# Processor.net
KiCad netlist of a schematic drawn in Altium Designer
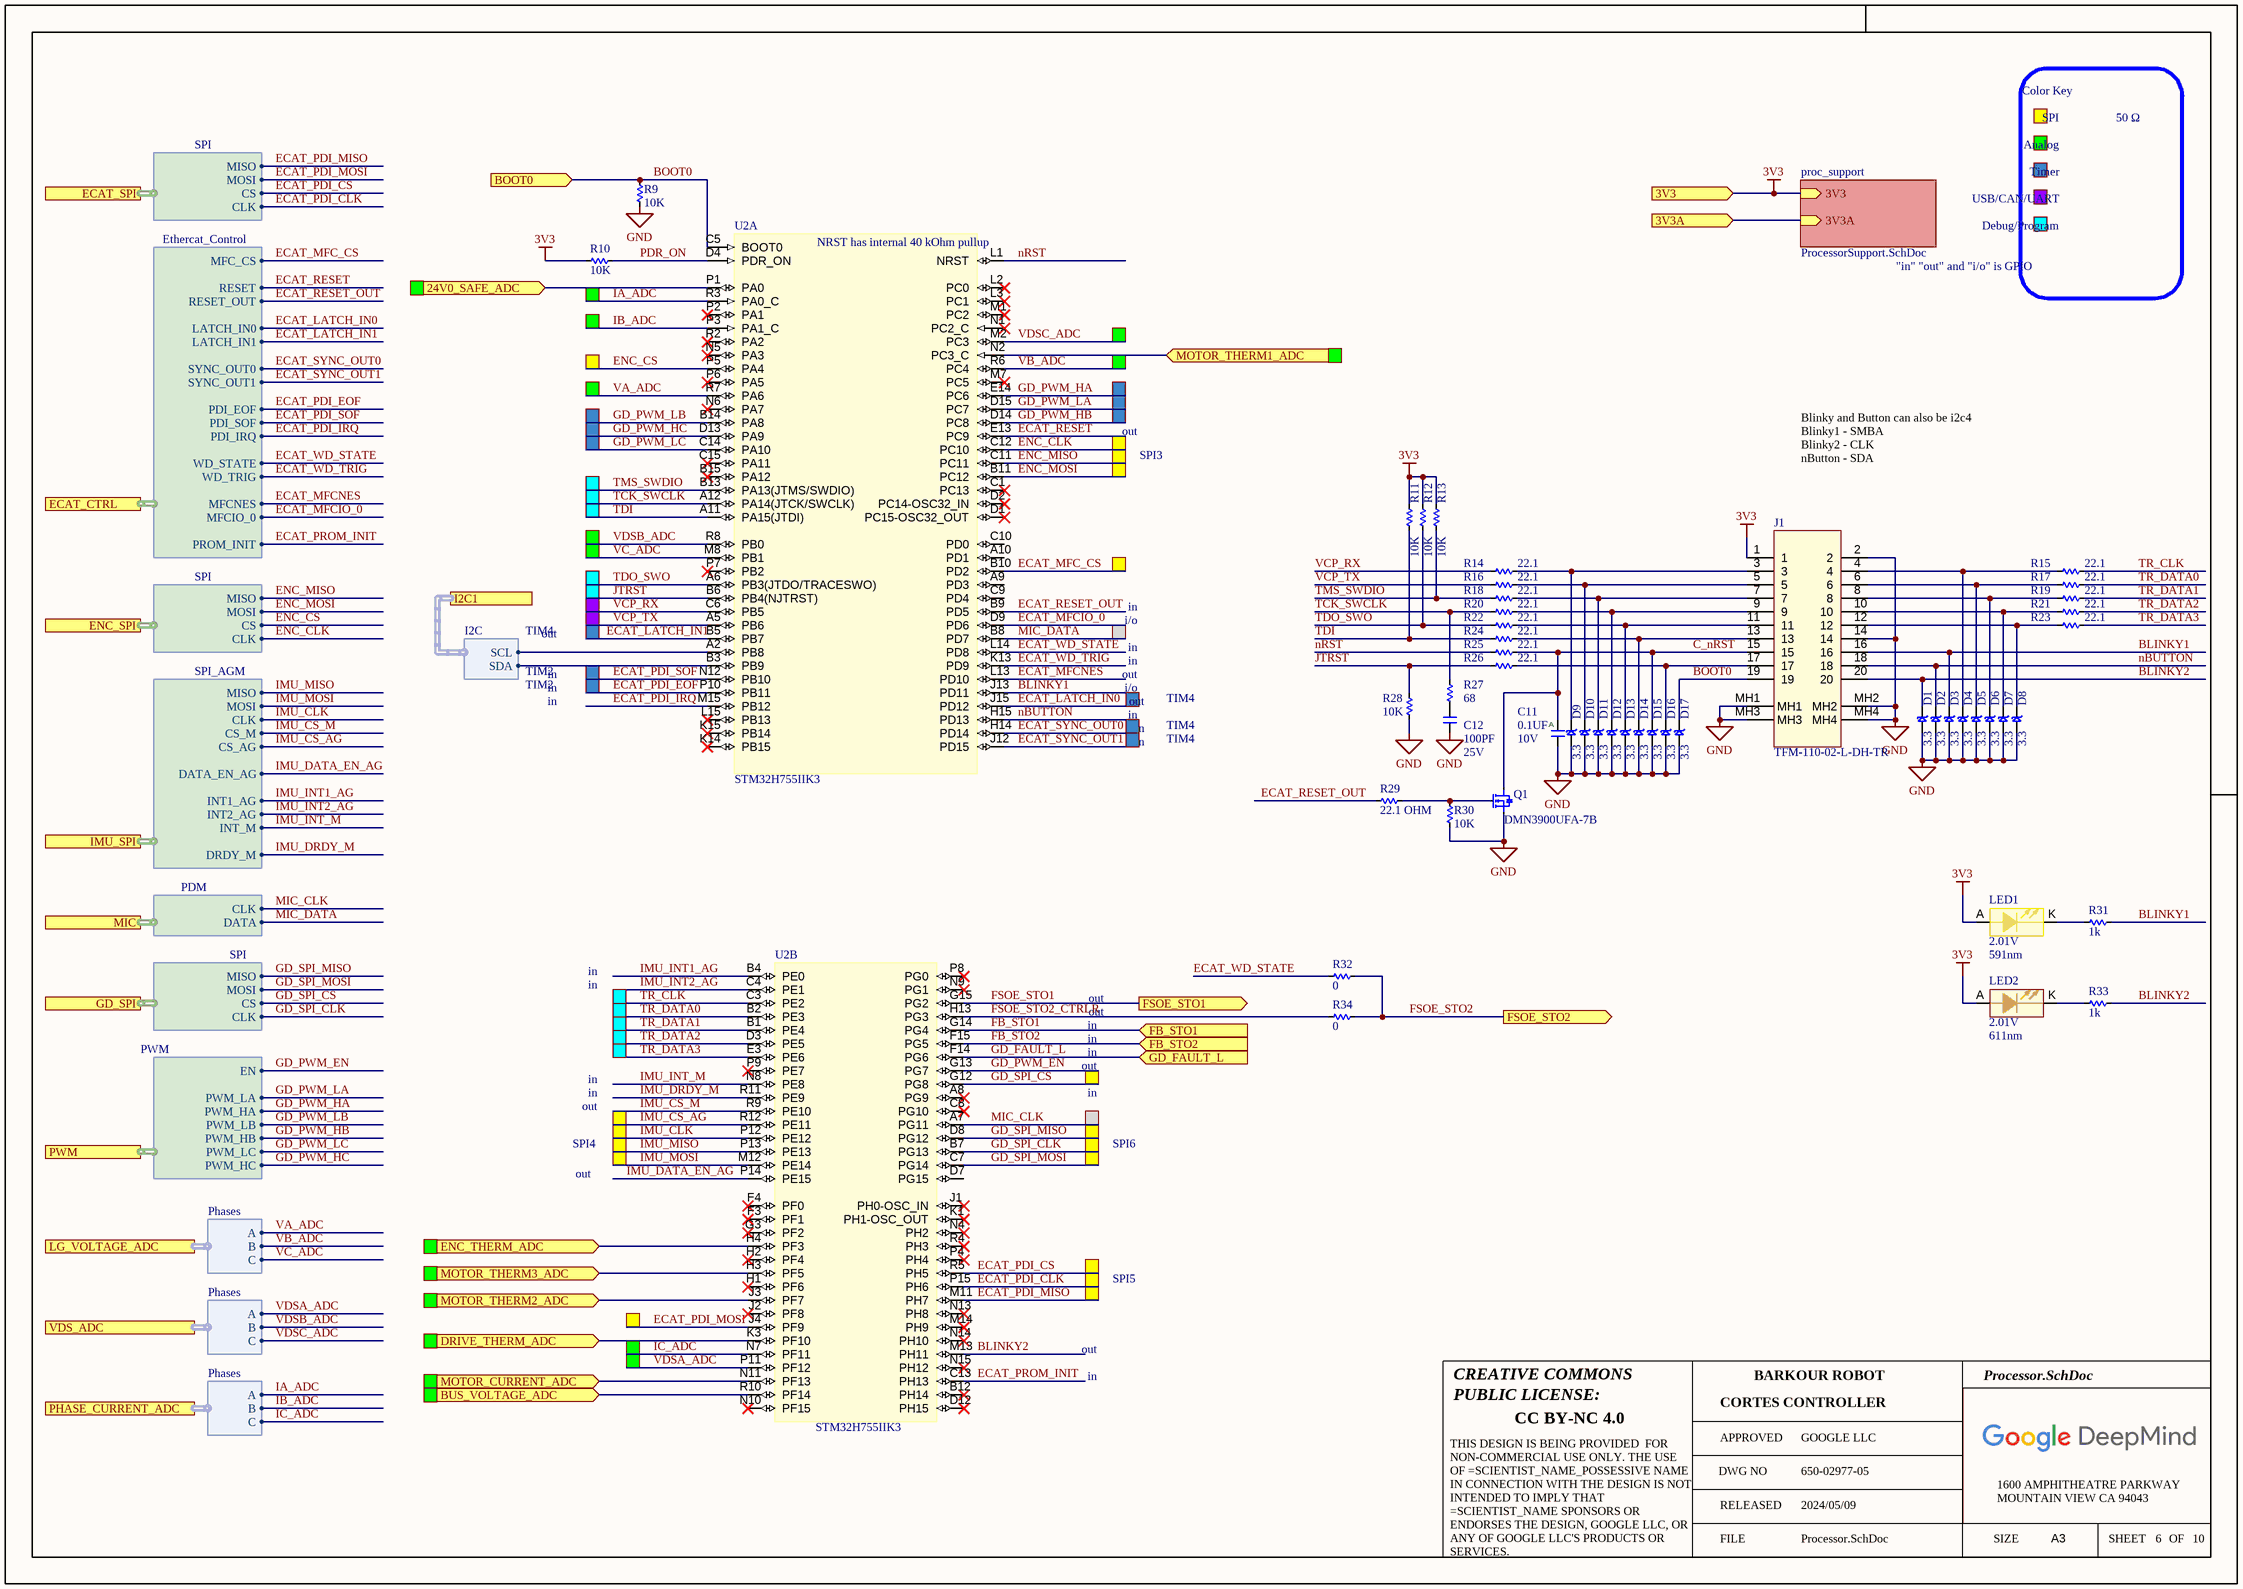
[diagram p0: Processor.SchDoc]

(export (version "E")
  (design (tool "Eeschema 10.0.6"))
  (components
    (comp (ref "C11")
      (value "0.1UF")
      (footprint "C0201Y")
      (description "CAP, CER, X6S, 0.1uF, 10V, 10%, 0201, AUTOGRADE")
      (fields (field (name "MFG") "MURATA") (field (name "VOLTAGE") "10V") (field (name "TOLERANCE") "10%"))
      (libsource (lib "AltiumReleaseLibDB") (part "__Template_Cap_Auto"))
    )
    (comp (ref "C12")
      (value "100PF")
      (footprint "C0201Y")
      (description "CAP, CER, X7R, 100pF, 25V, 10%, 0201, 0.33mm T")
      (fields (field (name "MFG") "MURATA") (field (name "VOLTAGE") "25V") (field (name "TOLERANCE") "10%"))
      (libsource (lib "AltiumReleaseLibDB") (part "__Template_Cap"))
    )
    (comp (ref "D1")
      (value "3.3")
      (footprint "SOD1060X40")
      (description "TVS, DIODE, UNIDIR, 3.3VRWM, 4.8VBR, 7.8VCL, SOD-923")
      (fields (field (name "MFG") "ON Semiconductor"))
      (libsource (lib "AltiumReleaseLibDB") (part "__Template_Diode_TVS_A/K"))
    )
    (comp (ref "D2")
      (value "3.3")
      (footprint "SOD1060X40")
      (description "TVS, DIODE, UNIDIR, 3.3VRWM, 4.8VBR, 7.8VCL, SOD-923")
      (fields (field (name "MFG") "ON Semiconductor"))
      (libsource (lib "AltiumReleaseLibDB") (part "__Template_Diode_TVS_A/K"))
    )
    (comp (ref "D3")
      (value "3.3")
      (footprint "SOD1060X40")
      (description "TVS, DIODE, UNIDIR, 3.3VRWM, 4.8VBR, 7.8VCL, SOD-923")
      (fields (field (name "MFG") "ON Semiconductor"))
      (libsource (lib "AltiumReleaseLibDB") (part "__Template_Diode_TVS_A/K"))
    )
    (comp (ref "D4")
      (value "3.3")
      (footprint "SOD1060X40")
      (description "TVS, DIODE, UNIDIR, 3.3VRWM, 4.8VBR, 7.8VCL, SOD-923")
      (fields (field (name "MFG") "ON Semiconductor"))
      (libsource (lib "AltiumReleaseLibDB") (part "__Template_Diode_TVS_A/K"))
    )
    (comp (ref "D5")
      (value "3.3")
      (footprint "SOD1060X40")
      (description "TVS, DIODE, UNIDIR, 3.3VRWM, 4.8VBR, 7.8VCL, SOD-923")
      (fields (field (name "MFG") "ON Semiconductor"))
      (libsource (lib "AltiumReleaseLibDB") (part "__Template_Diode_TVS_A/K"))
    )
    (comp (ref "D6")
      (value "3.3")
      (footprint "SOD1060X40")
      (description "TVS, DIODE, UNIDIR, 3.3VRWM, 4.8VBR, 7.8VCL, SOD-923")
      (fields (field (name "MFG") "ON Semiconductor"))
      (libsource (lib "AltiumReleaseLibDB") (part "__Template_Diode_TVS_A/K"))
    )
    (comp (ref "D7")
      (value "3.3")
      (footprint "SOD1060X40")
      (description "TVS, DIODE, UNIDIR, 3.3VRWM, 4.8VBR, 7.8VCL, SOD-923")
      (fields (field (name "MFG") "ON Semiconductor"))
      (libsource (lib "AltiumReleaseLibDB") (part "__Template_Diode_TVS_A/K"))
    )
    (comp (ref "D8")
      (value "3.3")
      (footprint "SOD1060X40")
      (description "TVS, DIODE, UNIDIR, 3.3VRWM, 4.8VBR, 7.8VCL, SOD-923")
      (fields (field (name "MFG") "ON Semiconductor"))
      (libsource (lib "AltiumReleaseLibDB") (part "__Template_Diode_TVS_A/K"))
    )
    (comp (ref "D9")
      (value "3.3")
      (footprint "SOD1060X40")
      (description "TVS, DIODE, UNIDIR, 3.3VRWM, 4.8VBR, 7.8VCL, SOD-923")
      (fields (field (name "MFG") "ON Semiconductor"))
      (libsource (lib "AltiumReleaseLibDB") (part "__Template_Diode_TVS_A/K"))
    )
    (comp (ref "D10")
      (value "3.3")
      (footprint "SOD1060X40")
      (description "TVS, DIODE, UNIDIR, 3.3VRWM, 4.8VBR, 7.8VCL, SOD-923")
      (fields (field (name "MFG") "ON Semiconductor"))
      (libsource (lib "AltiumReleaseLibDB") (part "__Template_Diode_TVS_A/K"))
    )
    (comp (ref "D11")
      (value "3.3")
      (footprint "SOD1060X40")
      (description "TVS, DIODE, UNIDIR, 3.3VRWM, 4.8VBR, 7.8VCL, SOD-923")
      (fields (field (name "MFG") "ON Semiconductor"))
      (libsource (lib "AltiumReleaseLibDB") (part "__Template_Diode_TVS_A/K"))
    )
    (comp (ref "D12")
      (value "3.3")
      (footprint "SOD1060X40")
      (description "TVS, DIODE, UNIDIR, 3.3VRWM, 4.8VBR, 7.8VCL, SOD-923")
      (fields (field (name "MFG") "ON Semiconductor"))
      (libsource (lib "AltiumReleaseLibDB") (part "__Template_Diode_TVS_A/K"))
    )
    (comp (ref "D13")
      (value "3.3")
      (footprint "SOD1060X40")
      (description "TVS, DIODE, UNIDIR, 3.3VRWM, 4.8VBR, 7.8VCL, SOD-923")
      (fields (field (name "MFG") "ON Semiconductor"))
      (libsource (lib "AltiumReleaseLibDB") (part "__Template_Diode_TVS_A/K"))
    )
    (comp (ref "D14")
      (value "3.3")
      (footprint "SOD1060X40")
      (description "TVS, DIODE, UNIDIR, 3.3VRWM, 4.8VBR, 7.8VCL, SOD-923")
      (fields (field (name "MFG") "ON Semiconductor"))
      (libsource (lib "AltiumReleaseLibDB") (part "__Template_Diode_TVS_A/K"))
    )
    (comp (ref "D15")
      (value "3.3")
      (footprint "SOD1060X40")
      (description "TVS, DIODE, UNIDIR, 3.3VRWM, 4.8VBR, 7.8VCL, SOD-923")
      (fields (field (name "MFG") "ON Semiconductor"))
      (libsource (lib "AltiumReleaseLibDB") (part "__Template_Diode_TVS_A/K"))
    )
    (comp (ref "D16")
      (value "3.3")
      (footprint "SOD1060X40")
      (description "TVS, DIODE, UNIDIR, 3.3VRWM, 4.8VBR, 7.8VCL, SOD-923")
      (fields (field (name "MFG") "ON Semiconductor"))
      (libsource (lib "AltiumReleaseLibDB") (part "__Template_Diode_TVS_A/K"))
    )
    (comp (ref "D17")
      (value "3.3")
      (footprint "SOD1060X40")
      (description "TVS, DIODE, UNIDIR, 3.3VRWM, 4.8VBR, 7.8VCL, SOD-923")
      (fields (field (name "MFG") "ON Semiconductor"))
      (libsource (lib "AltiumReleaseLibDB") (part "__Template_Diode_TVS_A/K"))
    )
    (comp (ref "J1")
      (value "~")
      (footprint "SAMTEC_TFM-110-02-L-DH")
      (description "CONN, HDR, SHRD, RA, 2x10, 1.27MM P, 6.02MM h, GOLD, TH")
      (fields (field (name "MFG") "Samtec Inc") (field (name "MFG P/N") "TFM-110-02-L-DH-TR"))
      (libsource (lib "AltiumReleaseLibDB") (part "__Template_Connector_2X10_4MH"))
    )
    (comp (ref "LED1")
      (value "__Template_LED_YELLOW_AK")
      (footprint "LED_APG0603SYC-TT")
      (description "LED, YELLOW, 591NM, 10mA, CLEAR, 0201")
      (fields
        (field (name "MFG") "Kingbright")
        (field (name "VOLTAGE – FORWARD (VF) (MAX) @ IF") "2.01V")
        (field (name "COLOR / WAVELENGTH") "591nm")
      )
      (libsource (lib "AltiumReleaseLibDB") (part "__Template_LED_YELLOW_AK"))
    )
    (comp (ref "LED2")
      (value "__Template_LED_ORANGE_AK")
      (footprint "LED_APG0603SYC-TT")
      (description "LED, ORANGE, 611NM, 10mA, CLEAR, 0201")
      (fields
        (field (name "MFG") "Kingbright")
        (field (name "VOLTAGE – FORWARD (VF) (MAX) @ IF") "2.01V")
        (field (name "COLOR / WAVELENGTH") "611nm")
      )
      (libsource (lib "AltiumReleaseLibDB") (part "__Template_LED_ORANGE_AK"))
    )
    (comp (ref "Q1")
      (value "NFET_DMN3900UFA")
      (footprint "3XDFN")
      (description "MOSFET, N-CH, 30V, 0.55A, DMN3900")
      (fields (field (name "MFG") "Diodes Incorporated") (field (name "MFG P/N") "DMN3900UFA-7B"))
      (libsource (lib "AltiumReleaseLibDB") (part "NFET_DMN3900UFA"))
    )
    (comp (ref "R9")
      (value "10K")
      (footprint "R0201_H0.26MM")
      (description "RES, 10K, 1%, 1/20W, 0201, AUTOGRADE")
      (fields (field (name "MFG") "PANASONIC") (field (name "POWER") "1/20W"))
      (libsource (lib "AltiumReleaseLibDB") (part "__Template_Resistor"))
    )
    (comp (ref "R10")
      (value "10K")
      (footprint "R0201_H0.26MM")
      (description "RES, 10K, 1%, 1/20W, 0201, AUTOGRADE")
      (fields (field (name "MFG") "PANASONIC") (field (name "POWER") "1/20W"))
      (libsource (lib "AltiumReleaseLibDB") (part "__Template_Resistor"))
    )
    (comp (ref "R11")
      (value "10K")
      (footprint "R0201_H0.26MM")
      (description "RES, 10K, 1%, 1/20W, 0201, AUTOGRADE")
      (fields (field (name "MFG") "PANASONIC") (field (name "POWER") "1/20W"))
      (libsource (lib "AltiumReleaseLibDB") (part "__Template_Resistor"))
    )
    (comp (ref "R12")
      (value "10K")
      (footprint "R0201_H0.26MM")
      (description "RES, 10K, 1%, 1/20W, 0201, AUTOGRADE")
      (fields (field (name "MFG") "PANASONIC") (field (name "POWER") "1/20W"))
      (libsource (lib "AltiumReleaseLibDB") (part "__Template_Resistor"))
    )
    (comp (ref "R13")
      (value "10K")
      (footprint "R0201_H0.26MM")
      (description "RES, 10K, 1%, 1/20W, 0201, AUTOGRADE")
      (fields (field (name "MFG") "PANASONIC") (field (name "POWER") "1/20W"))
      (libsource (lib "AltiumReleaseLibDB") (part "__Template_Resistor"))
    )
    (comp (ref "R14")
      (value "22.1")
      (footprint "R0201_H0.26MM")
      (description "RES, 22.1, 1%, 1/20W, 0201, AUTOGRADE")
      (fields (field (name "MFG") "Panasonic Electronic Components") (field (name "POWER") "0.05W, 1/20W"))
      (libsource (lib "AltiumReleaseLibDB") (part "__Template_Resistor"))
    )
    (comp (ref "R15")
      (value "22.1")
      (footprint "R0201_H0.26MM")
      (description "RES, 22.1, 1%, 1/20W, 0201, AUTOGRADE")
      (fields (field (name "MFG") "Panasonic Electronic Components") (field (name "POWER") "0.05W, 1/20W"))
      (libsource (lib "AltiumReleaseLibDB") (part "__Template_Resistor"))
    )
    (comp (ref "R16")
      (value "22.1")
      (footprint "R0201_H0.26MM")
      (description "RES, 22.1, 1%, 1/20W, 0201, AUTOGRADE")
      (fields (field (name "MFG") "Panasonic Electronic Components") (field (name "POWER") "0.05W, 1/20W"))
      (libsource (lib "AltiumReleaseLibDB") (part "__Template_Resistor"))
    )
    (comp (ref "R17")
      (value "22.1")
      (footprint "R0201_H0.26MM")
      (description "RES, 22.1, 1%, 1/20W, 0201, AUTOGRADE")
      (fields (field (name "MFG") "Panasonic Electronic Components") (field (name "POWER") "0.05W, 1/20W"))
      (libsource (lib "AltiumReleaseLibDB") (part "__Template_Resistor"))
    )
    (comp (ref "R18")
      (value "22.1")
      (footprint "R0201_H0.26MM")
      (description "RES, 22.1, 1%, 1/20W, 0201, AUTOGRADE")
      (fields (field (name "MFG") "Panasonic Electronic Components") (field (name "POWER") "0.05W, 1/20W"))
      (libsource (lib "AltiumReleaseLibDB") (part "__Template_Resistor"))
    )
    (comp (ref "R19")
      (value "22.1")
      (footprint "R0201_H0.26MM")
      (description "RES, 22.1, 1%, 1/20W, 0201, AUTOGRADE")
      (fields (field (name "MFG") "Panasonic Electronic Components") (field (name "POWER") "0.05W, 1/20W"))
      (libsource (lib "AltiumReleaseLibDB") (part "__Template_Resistor"))
    )
    (comp (ref "R20")
      (value "22.1")
      (footprint "R0201_H0.26MM")
      (description "RES, 22.1, 1%, 1/20W, 0201, AUTOGRADE")
      (fields (field (name "MFG") "Panasonic Electronic Components") (field (name "POWER") "0.05W, 1/20W"))
      (libsource (lib "AltiumReleaseLibDB") (part "__Template_Resistor"))
    )
    (comp (ref "R21")
      (value "22.1")
      (footprint "R0201_H0.26MM")
      (description "RES, 22.1, 1%, 1/20W, 0201, AUTOGRADE")
      (fields (field (name "MFG") "Panasonic Electronic Components") (field (name "POWER") "0.05W, 1/20W"))
      (libsource (lib "AltiumReleaseLibDB") (part "__Template_Resistor"))
    )
    (comp (ref "R22")
      (value "22.1")
      (footprint "R0201_H0.26MM")
      (description "RES, 22.1, 1%, 1/20W, 0201, AUTOGRADE")
      (fields (field (name "MFG") "Panasonic Electronic Components") (field (name "POWER") "0.05W, 1/20W"))
      (libsource (lib "AltiumReleaseLibDB") (part "__Template_Resistor"))
    )
    (comp (ref "R23")
      (value "22.1")
      (footprint "R0201_H0.26MM")
      (description "RES, 22.1, 1%, 1/20W, 0201, AUTOGRADE")
      (fields (field (name "MFG") "Panasonic Electronic Components") (field (name "POWER") "0.05W, 1/20W"))
      (libsource (lib "AltiumReleaseLibDB") (part "__Template_Resistor"))
    )
    (comp (ref "R24")
      (value "22.1")
      (footprint "R0201_H0.26MM")
      (description "RES, 22.1, 1%, 1/20W, 0201, AUTOGRADE")
      (fields (field (name "MFG") "Panasonic Electronic Components") (field (name "POWER") "0.05W, 1/20W"))
      (libsource (lib "AltiumReleaseLibDB") (part "__Template_Resistor"))
    )
    (comp (ref "R25")
      (value "22.1")
      (footprint "R0201_H0.26MM")
      (description "RES, 22.1, 1%, 1/20W, 0201, AUTOGRADE")
      (fields (field (name "MFG") "Panasonic Electronic Components") (field (name "POWER") "0.05W, 1/20W"))
      (libsource (lib "AltiumReleaseLibDB") (part "__Template_Resistor"))
    )
    (comp (ref "R26")
      (value "22.1")
      (footprint "R0201_H0.26MM")
      (description "RES, 22.1, 1%, 1/20W, 0201, AUTOGRADE")
      (fields (field (name "MFG") "Panasonic Electronic Components") (field (name "POWER") "0.05W, 1/20W"))
      (libsource (lib "AltiumReleaseLibDB") (part "__Template_Resistor"))
    )
    (comp (ref "R27")
      (value "68")
      (footprint "R0201_H0.26MM")
      (description "RES, 68, 1%, 1/20W, 0201, AUTOGRADE")
      (fields (field (name "MFG") "Panasonic Electronic Components") (field (name "POWER") "0.05W, 1/20W"))
      (libsource (lib "AltiumReleaseLibDB") (part "__Template_Resistor"))
    )
    (comp (ref "R28")
      (value "10K")
      (footprint "R0201_H0.26MM")
      (description "RES, 10K, 1%, 1/20W, 0201, AUTOGRADE")
      (fields (field (name "MFG") "PANASONIC") (field (name "POWER") "1/20W"))
      (libsource (lib "AltiumReleaseLibDB") (part "__Template_Resistor"))
    )
    (comp (ref "R29")
      (value "22.1 OHM")
      (footprint "R0201_H0.26MM")
      (description "RES, 22.1, 1%, 1/20W, 0201, AUTOGRADE")
      (fields (field (name "MFG") "Panasonic Electronic Components") (field (name "POWER") "0.05W, 1/20W"))
      (libsource (lib "AltiumReleaseLibDB") (part "__Template_Resistor"))
    )
    (comp (ref "R30")
      (value "10K")
      (footprint "R0201_H0.26MM")
      (description "RES, 10K, 1%, 1/20W, 0201, AUTOGRADE")
      (fields (field (name "MFG") "PANASONIC") (field (name "POWER") "1/20W"))
      (libsource (lib "AltiumReleaseLibDB") (part "__Template_Resistor"))
    )
    (comp (ref "R31")
      (value "1k")
      (footprint "R0201_H0.26MM")
      (description "RES, 1K, 1%, 1/20W, 0201, AUTOGRADE")
      (fields (field (name "MFG") "Bourns Inc.") (field (name "POWER") "0.05W, 1/20W"))
      (libsource (lib "AltiumReleaseLibDB") (part "__Template_Resistor"))
    )
    (comp (ref "R32")
      (value "0")
      (footprint "R0603")
      (description "RES, JUMPER, 0, 1/10W, 0603")
      (fields (field (name "MFG") "ROHM") (field (name "POWER") "1/10W"))
      (libsource (lib "AltiumReleaseLibDB") (part "__Template_Resistor"))
    )
    (comp (ref "R33")
      (value "1k")
      (footprint "R0201_H0.26MM")
      (description "RES, 1K, 1%, 1/20W, 0201, AUTOGRADE")
      (fields (field (name "MFG") "Bourns Inc.") (field (name "POWER") "0.05W, 1/20W"))
      (libsource (lib "AltiumReleaseLibDB") (part "__Template_Resistor"))
    )
    (comp (ref "R34")
      (value "0")
      (footprint "R0603")
      (description "RES, JUMPER, 0, 1/10W, 0603")
      (fields (field (name "MFG") "ROHM") (field (name "POWER") "1/10W"))
      (libsource (lib "AltiumReleaseLibDB") (part "__Template_Resistor"))
    )
    (comp (ref "U2")
      (value "MCU_STM32H755IIK3")
      (footprint "BGS201C65P15X15_1000X1000X60")
      (description "IC, MCU, STM32H755xI, ARM, 32-BIT, 240MHZ, 128 I/O, 2MB, FLASH, 1.62V TO 3.6V, UFBGA-201")
      (fields (field (name "MFG") "STMicroelectronics") (field (name "MFG P/N") "STM32H755IIK3"))
      (libsource (lib "AltiumReleaseLibDB") (part "MCU_STM32H755IIK3"))
    )
  )
  (nets
    (net (code "9") (name "/24V0_SAFE_ADC") (class "Default")
      (node (ref "U2") (pin "P1") (pinfunction "PA0_P1") (pintype "bidirectional"))
    )
    (net (code "10") (name "/BLINKY1") (class "Default")
      (node (ref "D3") (pin "K") (pinfunction "K_K") (pintype "passive"))
      (node (ref "J1") (pin "16") (pinfunction "16_16") (pintype "passive"))
      (node (ref "R31") (pin "1") (pintype "passive"))
      (node (ref "U2") (pin "J13") (pinfunction "PD11_J13") (pintype "bidirectional"))
    )
    (net (code "11") (name "/BLINKY2") (class "Default")
      (node (ref "D1") (pin "K") (pinfunction "K_K") (pintype "passive"))
      (node (ref "J1") (pin "20") (pinfunction "20_20") (pintype "passive"))
      (node (ref "R33") (pin "1") (pintype "passive"))
      (node (ref "U2") (pin "M13") (pinfunction "PH11_M13") (pintype "bidirectional"))
    )
    (net (code "12") (name "/BOOT0") (class "Default")
      (node (ref "D17") (pin "K") (pinfunction "K_K") (pintype "passive"))
      (node (ref "J1") (pin "19") (pinfunction "19_19") (pintype "passive"))
      (node (ref "R9") (pin "2") (pintype "passive"))
      (node (ref "U2") (pin "C5") (pinfunction "BOOT0_C5") (pintype "input"))
    )
    (net (code "13") (name "/BUS_VOLTAGE_ADC") (class "Default")
      (node (ref "U2") (pin "R10") (pinfunction "PF14_R10") (pintype "bidirectional"))
    )
    (net (code "14") (name "/C_nRST") (class "Default")
      (node (ref "C11") (pin "1") (pintype "passive"))
      (node (ref "D15") (pin "K") (pinfunction "K_K") (pintype "passive"))
      (node (ref "J1") (pin "15") (pinfunction "15_15") (pintype "passive"))
      (node (ref "Q1") (pin "3") (pinfunction "D_3") (pintype "passive"))
      (node (ref "R25") (pin "2") (pintype "passive"))
    )
    (net (code "15") (name "/DRIVE_THERM_ADC") (class "Default")
      (node (ref "U2") (pin "K3") (pinfunction "PF10_K3") (pintype "bidirectional"))
    )
    (net (code "16") (name "/ECAT_LATCH_IN0") (class "Default")
      (node (ref "U2") (pin "J15") (pinfunction "PD12_J15") (pintype "bidirectional"))
    )
    (net (code "17") (name "/ECAT_LATCH_IN1") (class "Default")
      (node (ref "U2") (pin "B5") (pinfunction "PB7_B5") (pintype "bidirectional"))
    )
    (net (code "18") (name "/ECAT_MFCIO_0") (class "Default")
      (node (ref "U2") (pin "D9") (pinfunction "PD6_D9") (pintype "bidirectional"))
    )
    (net (code "19") (name "/ECAT_MFCNES") (class "Default")
      (node (ref "U2") (pin "L13") (pinfunction "PD10_L13") (pintype "bidirectional"))
    )
    (net (code "20") (name "/ECAT_MFC_CS") (class "Default")
      (node (ref "U2") (pin "B10") (pinfunction "PD2_B10") (pintype "bidirectional"))
    )
    (net (code "21") (name "/ECAT_PDI_CLK") (class "Default")
      (node (ref "U2") (pin "P15") (pinfunction "PH6_P15") (pintype "bidirectional"))
    )
    (net (code "22") (name "/ECAT_PDI_CS") (class "Default")
      (node (ref "U2") (pin "R5") (pinfunction "PH5_R5") (pintype "bidirectional"))
    )
    (net (code "23") (name "/ECAT_PDI_EOF") (class "Default")
      (node (ref "U2") (pin "P10") (pinfunction "PB11_P10") (pintype "bidirectional"))
    )
    (net (code "24") (name "/ECAT_PDI_IRQ") (class "Default")
      (node (ref "U2") (pin "M15") (pinfunction "PB12_M15") (pintype "bidirectional"))
    )
    (net (code "25") (name "/ECAT_PDI_MISO") (class "Default")
      (node (ref "U2") (pin "M11") (pinfunction "PH7_M11") (pintype "bidirectional"))
    )
    (net (code "26") (name "/ECAT_PDI_MOSI") (class "Default")
      (node (ref "U2") (pin "J4") (pinfunction "PF9_J4") (pintype "bidirectional"))
    )
    (net (code "27") (name "/ECAT_PDI_SOF") (class "Default")
      (node (ref "U2") (pin "N12") (pinfunction "PB10_N12") (pintype "bidirectional"))
    )
    (net (code "28") (name "/ECAT_PROM_INIT") (class "Default")
      (node (ref "U2") (pin "C13") (pinfunction "PH13_C13") (pintype "bidirectional"))
    )
    (net (code "29") (name "/ECAT_RESET") (class "Default")
      (node (ref "U2") (pin "E13") (pinfunction "PC9_E13") (pintype "bidirectional"))
    )
    (net (code "30") (name "/ECAT_RESET_OUT") (class "Default")
      (node (ref "R29") (pin "1") (pintype "passive"))
      (node (ref "U2") (pin "B9") (pinfunction "PD5_B9") (pintype "bidirectional"))
    )
    (net (code "31") (name "/ECAT_SYNC_OUT0") (class "Default")
      (node (ref "U2") (pin "H14") (pinfunction "PD14_H14") (pintype "bidirectional"))
    )
    (net (code "32") (name "/ECAT_SYNC_OUT1") (class "Default")
      (node (ref "U2") (pin "J12") (pinfunction "PD15_J12") (pintype "bidirectional"))
    )
    (net (code "33") (name "/ECAT_WD_STATE") (class "Default")
      (node (ref "R32") (pin "2") (pintype "passive"))
      (node (ref "U2") (pin "L14") (pinfunction "PD8_L14") (pintype "bidirectional"))
    )
    (net (code "34") (name "/ECAT_WD_TRIG") (class "Default")
      (node (ref "U2") (pin "K13") (pinfunction "PD9_K13") (pintype "bidirectional"))
    )
    (net (code "35") (name "/ENC_CLK") (class "Default")
      (node (ref "U2") (pin "C12") (pinfunction "PC10_C12") (pintype "bidirectional"))
    )
    (net (code "36") (name "/ENC_CS") (class "Default")
      (node (ref "U2") (pin "P5") (pinfunction "PA4_P5") (pintype "bidirectional"))
    )
    (net (code "37") (name "/ENC_MISO") (class "Default")
      (node (ref "U2") (pin "C11") (pinfunction "PC11_C11") (pintype "bidirectional"))
    )
    (net (code "38") (name "/ENC_MOSI") (class "Default")
      (node (ref "U2") (pin "B11") (pinfunction "PC12_B11") (pintype "bidirectional"))
    )
    (net (code "39") (name "/ENC_THERM_ADC") (class "Default")
      (node (ref "U2") (pin "H4") (pinfunction "PF3_H4") (pintype "bidirectional"))
    )
    (net (code "40") (name "/FB_STO1") (class "Default")
      (node (ref "U2") (pin "G14") (pinfunction "PG4_G14") (pintype "bidirectional"))
    )
    (net (code "41") (name "/FB_STO2") (class "Default")
      (node (ref "U2") (pin "F15") (pinfunction "PG5_F15") (pintype "bidirectional"))
    )
    (net (code "42") (name "/FSOE_STO1") (class "Default")
      (node (ref "U2") (pin "G15") (pinfunction "PG2_G15") (pintype "bidirectional"))
    )
    (net (code "43") (name "/FSOE_STO2") (class "Default")
      (node (ref "R32") (pin "1") (pintype "passive"))
      (node (ref "R34") (pin "1") (pintype "passive"))
    )
    (net (code "44") (name "/FSOE_STO2_CTRLR") (class "Default")
      (node (ref "R34") (pin "2") (pintype "passive"))
      (node (ref "U2") (pin "H13") (pinfunction "PG3_H13") (pintype "bidirectional"))
    )
    (net (code "45") (name "/GD_FAULT_L") (class "Default")
      (node (ref "U2") (pin "F14") (pinfunction "PG6_F14") (pintype "bidirectional"))
    )
    (net (code "46") (name "/GD_PWM_EN") (class "Default")
      (node (ref "U2") (pin "G13") (pinfunction "PG7_G13") (pintype "bidirectional"))
    )
    (net (code "47") (name "/GD_PWM_HA") (class "Default")
      (node (ref "U2") (pin "E14") (pinfunction "PC6_E14") (pintype "bidirectional"))
    )
    (net (code "48") (name "/GD_PWM_HB") (class "Default")
      (node (ref "U2") (pin "D14") (pinfunction "PC8_D14") (pintype "bidirectional"))
    )
    (net (code "49") (name "/GD_PWM_HC") (class "Default")
      (node (ref "U2") (pin "D13") (pinfunction "PA9_D13") (pintype "bidirectional"))
    )
    (net (code "50") (name "/GD_PWM_LA") (class "Default")
      (node (ref "U2") (pin "D15") (pinfunction "PC7_D15") (pintype "bidirectional"))
    )
    (net (code "51") (name "/GD_PWM_LB") (class "Default")
      (node (ref "U2") (pin "B14") (pinfunction "PA8_B14") (pintype "bidirectional"))
    )
    (net (code "52") (name "/GD_PWM_LC") (class "Default")
      (node (ref "U2") (pin "C14") (pinfunction "PA10_C14") (pintype "bidirectional"))
    )
    (net (code "53") (name "/GD_SPI_CLK") (class "Default")
      (node (ref "U2") (pin "B7") (pinfunction "PG13_B7") (pintype "bidirectional"))
    )
    (net (code "54") (name "/GD_SPI_CS") (class "Default")
      (node (ref "U2") (pin "G12") (pinfunction "PG8_G12") (pintype "bidirectional"))
    )
    (net (code "55") (name "/GD_SPI_MISO") (class "Default")
      (node (ref "U2") (pin "D8") (pinfunction "PG12_D8") (pintype "bidirectional"))
    )
    (net (code "56") (name "/GD_SPI_MOSI") (class "Default")
      (node (ref "U2") (pin "C7") (pinfunction "PG14_C7") (pintype "bidirectional"))
    )
    (net (code "57") (name "/IA_ADC") (class "Default")
      (node (ref "U2") (pin "R3") (pinfunction "PA0_C_R3") (pintype "input"))
    )
    (net (code "58") (name "/IB_ADC") (class "Default")
      (node (ref "U2") (pin "P3") (pinfunction "PA1_C_P3") (pintype "input"))
    )
    (net (code "59") (name "/IC_ADC") (class "Default")
      (node (ref "U2") (pin "N7") (pinfunction "PF11_N7") (pintype "bidirectional"))
    )
    (net (code "60") (name "/IMU_CLK") (class "Default")
      (node (ref "U2") (pin "P12") (pinfunction "PE12_P12") (pintype "bidirectional"))
    )
    (net (code "61") (name "/IMU_CS_AG") (class "Default")
      (node (ref "U2") (pin "R12") (pinfunction "PE11_R12") (pintype "bidirectional"))
    )
    (net (code "62") (name "/IMU_CS_M") (class "Default")
      (node (ref "U2") (pin "R9") (pinfunction "PE10_R9") (pintype "bidirectional"))
    )
    (net (code "63") (name "/IMU_DATA_EN_AG") (class "Default")
      (node (ref "U2") (pin "P14") (pinfunction "PE15_P14") (pintype "bidirectional"))
    )
    (net (code "64") (name "/IMU_DRDY_M") (class "Default")
      (node (ref "U2") (pin "R11") (pinfunction "PE9_R11") (pintype "bidirectional"))
    )
    (net (code "65") (name "/IMU_INT1_AG") (class "Default")
      (node (ref "U2") (pin "B4") (pinfunction "PE0_B4") (pintype "bidirectional"))
    )
    (net (code "66") (name "/IMU_INT2_AG") (class "Default")
      (node (ref "U2") (pin "C4") (pinfunction "PE1_C4") (pintype "bidirectional"))
    )
    (net (code "67") (name "/IMU_INT_M") (class "Default")
      (node (ref "U2") (pin "N8") (pinfunction "PE8_N8") (pintype "bidirectional"))
    )
    (net (code "68") (name "/IMU_MISO") (class "Default")
      (node (ref "U2") (pin "P13") (pinfunction "PE13_P13") (pintype "bidirectional"))
    )
    (net (code "69") (name "/IMU_MOSI") (class "Default")
      (node (ref "U2") (pin "M12") (pinfunction "PE14_M12") (pintype "bidirectional"))
    )
    (net (code "70") (name "/JTRST") (class "Default")
      (node (ref "R26") (pin "1") (pintype "passive"))
      (node (ref "R28") (pin "2") (pintype "passive"))
      (node (ref "U2") (pin "B6") (pinfunction "PB4(NJTRST)_B6") (pintype "bidirectional"))
    )
    (net (code "71") (name "/MIC_CLK") (class "Default")
      (node (ref "U2") (pin "A7") (pinfunction "PG11_A7") (pintype "bidirectional"))
    )
    (net (code "72") (name "/MIC_DATA") (class "Default")
      (node (ref "U2") (pin "B8") (pinfunction "PD7_B8") (pintype "bidirectional"))
    )
    (net (code "73") (name "/MOTOR_CURRENT_ADC") (class "Default")
      (node (ref "U2") (pin "N11") (pinfunction "PF13_N11") (pintype "bidirectional"))
    )
    (net (code "74") (name "/MOTOR_THERM1_ADC") (class "Default")
      (node (ref "U2") (pin "N2") (pinfunction "PC3_C_N2") (pintype "input"))
    )
    (net (code "75") (name "/MOTOR_THERM2_ADC") (class "Default")
      (node (ref "U2") (pin "J3") (pinfunction "PF7_J3") (pintype "bidirectional"))
    )
    (net (code "76") (name "/MOTOR_THERM3_ADC") (class "Default")
      (node (ref "U2") (pin "H3") (pinfunction "PF5_H3") (pintype "bidirectional"))
    )
    (net (code "77") (name "/PDR_ON") (class "Default")
      (node (ref "R10") (pin "1") (pintype "passive"))
      (node (ref "U2") (pin "D4") (pinfunction "PDR_ON_D4") (pintype "input"))
    )
    (net (code "78") (name "/SCL") (class "Default")
      (node (ref "U2") (pin "A2") (pinfunction "PB8_A2") (pintype "bidirectional"))
    )
    (net (code "79") (name "/SDA") (class "Default")
      (node (ref "U2") (pin "B3") (pinfunction "PB9_B3") (pintype "bidirectional"))
    )
    (net (code "80") (name "/TCK_SWCLK") (class "Default")
      (node (ref "R20") (pin "1") (pintype "passive"))
      (node (ref "R27") (pin "2") (pintype "passive"))
      (node (ref "U2") (pin "A12") (pinfunction "PA14(JTCK/SWCLK)_A12") (pintype "bidirectional"))
    )
    (net (code "81") (name "/TDI") (class "Default")
      (node (ref "R11") (pin "1") (pintype "passive"))
      (node (ref "R24") (pin "1") (pintype "passive"))
      (node (ref "U2") (pin "A11") (pinfunction "PA15(JTDI)_A11") (pintype "bidirectional"))
    )
    (net (code "82") (name "/TDO_SWO") (class "Default")
      (node (ref "R12") (pin "1") (pintype "passive"))
      (node (ref "R22") (pin "1") (pintype "passive"))
      (node (ref "U2") (pin "A6") (pinfunction "PB3(JTDO/TRACESWO)_A6") (pintype "bidirectional"))
    )
    (net (code "83") (name "/TMS_SWDIO") (class "Default")
      (node (ref "R13") (pin "1") (pintype "passive"))
      (node (ref "R18") (pin "1") (pintype "passive"))
      (node (ref "U2") (pin "B13") (pinfunction "PA13(JTMS/SWDIO)_B13") (pintype "bidirectional"))
    )
    (net (code "84") (name "/TR_CLK") (class "Default")
      (node (ref "R15") (pin "2") (pintype "passive"))
      (node (ref "U2") (pin "C3") (pinfunction "PE2_C3") (pintype "bidirectional"))
    )
    (net (code "85") (name "/TR_DATA0") (class "Default")
      (node (ref "R17") (pin "2") (pintype "passive"))
      (node (ref "U2") (pin "B2") (pinfunction "PE3_B2") (pintype "bidirectional"))
    )
    (net (code "86") (name "/TR_DATA1") (class "Default")
      (node (ref "R19") (pin "2") (pintype "passive"))
      (node (ref "U2") (pin "B1") (pinfunction "PE4_B1") (pintype "bidirectional"))
    )
    (net (code "87") (name "/TR_DATA2") (class "Default")
      (node (ref "R21") (pin "2") (pintype "passive"))
      (node (ref "U2") (pin "D3") (pinfunction "PE5_D3") (pintype "bidirectional"))
    )
    (net (code "88") (name "/TR_DATA3") (class "Default")
      (node (ref "R23") (pin "2") (pintype "passive"))
      (node (ref "U2") (pin "E3") (pinfunction "PE6_E3") (pintype "bidirectional"))
    )
    (net (code "89") (name "/VA_ADC") (class "Default")
      (node (ref "U2") (pin "R7") (pinfunction "PA6_R7") (pintype "bidirectional"))
    )
    (net (code "90") (name "/VB_ADC") (class "Default")
      (node (ref "U2") (pin "R6") (pinfunction "PC4_R6") (pintype "bidirectional"))
    )
    (net (code "91") (name "/VCP_RX") (class "Default")
      (node (ref "R14") (pin "1") (pintype "passive"))
      (node (ref "U2") (pin "C6") (pinfunction "PB5_C6") (pintype "bidirectional"))
    )
    (net (code "92") (name "/VCP_TX") (class "Default")
      (node (ref "R16") (pin "1") (pintype "passive"))
      (node (ref "U2") (pin "A5") (pinfunction "PB6_A5") (pintype "bidirectional"))
    )
    (net (code "93") (name "/VC_ADC") (class "Default")
      (node (ref "U2") (pin "M8") (pinfunction "PB1_M8") (pintype "bidirectional"))
    )
    (net (code "94") (name "/VDSA_ADC") (class "Default")
      (node (ref "U2") (pin "P11") (pinfunction "PF12_P11") (pintype "bidirectional"))
    )
    (net (code "95") (name "/VDSB_ADC") (class "Default")
      (node (ref "U2") (pin "R8") (pinfunction "PB0_R8") (pintype "bidirectional"))
    )
    (net (code "96") (name "/VDSC_ADC") (class "Default")
      (node (ref "U2") (pin "M2") (pinfunction "PC3_M2") (pintype "bidirectional"))
    )
    (net (code "97") (name "/nBUTTON") (class "Default")
      (node (ref "D2") (pin "K") (pinfunction "K_K") (pintype "passive"))
      (node (ref "J1") (pin "18") (pinfunction "18_18") (pintype "passive"))
      (node (ref "U2") (pin "H15") (pinfunction "PD13_H15") (pintype "bidirectional"))
    )
    (net (code "98") (name "/nRST") (class "Default")
      (node (ref "R25") (pin "1") (pintype "passive"))
      (node (ref "U2") (pin "L1") (pinfunction "NRST_L1") (pintype "bidirectional"))
    )
    (net (code "106") (name "3V3") (class "Default")
      (node (ref "J1") (pin "1") (pinfunction "1_1") (pintype "passive"))
      (node (ref "LED1") (pin "A") (pinfunction "A_A") (pintype "passive"))
      (node (ref "LED2") (pin "A") (pinfunction "A_A") (pintype "passive"))
      (node (ref "R10") (pin "2") (pintype "passive"))
      (node (ref "R11") (pin "2") (pintype "passive"))
      (node (ref "R12") (pin "2") (pintype "passive"))
      (node (ref "R13") (pin "2") (pintype "passive"))
    )
    (net (code "107") (name "GND") (class "Default")
      (node (ref "C11") (pin "2") (pintype "passive"))
      (node (ref "C12") (pin "2") (pintype "passive"))
      (node (ref "D1") (pin "A") (pinfunction "A_A") (pintype "passive"))
      (node (ref "D10") (pin "A") (pinfunction "A_A") (pintype "passive"))
      (node (ref "D11") (pin "A") (pinfunction "A_A") (pintype "passive"))
      (node (ref "D12") (pin "A") (pinfunction "A_A") (pintype "passive"))
      (node (ref "D13") (pin "A") (pinfunction "A_A") (pintype "passive"))
      (node (ref "D14") (pin "A") (pinfunction "A_A") (pintype "passive"))
      (node (ref "D15") (pin "A") (pinfunction "A_A") (pintype "passive"))
      (node (ref "D16") (pin "A") (pinfunction "A_A") (pintype "passive"))
      (node (ref "D17") (pin "A") (pinfunction "A_A") (pintype "passive"))
      (node (ref "D2") (pin "A") (pinfunction "A_A") (pintype "passive"))
      (node (ref "D3") (pin "A") (pinfunction "A_A") (pintype "passive"))
      (node (ref "D4") (pin "A") (pinfunction "A_A") (pintype "passive"))
      (node (ref "D5") (pin "A") (pinfunction "A_A") (pintype "passive"))
      (node (ref "D6") (pin "A") (pinfunction "A_A") (pintype "passive"))
      (node (ref "D7") (pin "A") (pinfunction "A_A") (pintype "passive"))
      (node (ref "D8") (pin "A") (pinfunction "A_A") (pintype "passive"))
      (node (ref "D9") (pin "A") (pinfunction "A_A") (pintype "passive"))
      (node (ref "J1") (pin "14") (pinfunction "14_14") (pintype "passive"))
      (node (ref "J1") (pin "2") (pinfunction "2_2") (pintype "passive"))
      (node (ref "J1") (pin "MH1") (pinfunction "MH1_MH1") (pintype "passive"))
      (node (ref "J1") (pin "MH2") (pinfunction "MH2_MH2") (pintype "passive"))
      (node (ref "J1") (pin "MH3") (pinfunction "MH3_MH3") (pintype "passive"))
      (node (ref "J1") (pin "MH4") (pinfunction "MH4_MH4") (pintype "passive"))
      (node (ref "Q1") (pin "2") (pinfunction "S_2") (pintype "passive"))
      (node (ref "R28") (pin "1") (pintype "passive"))
      (node (ref "R30") (pin "1") (pintype "passive"))
      (node (ref "R9") (pin "1") (pintype "passive"))
    )
    (net (code "108") (name "Net-(C12-Pad1)") (class "Default")
      (node (ref "C12") (pin "1") (pintype "passive"))
      (node (ref "R27") (pin "1") (pintype "passive"))
    )
    (net (code "109") (name "Net-(D4-PadK)") (class "Default")
      (node (ref "D4") (pin "K") (pinfunction "K_K") (pintype "passive"))
      (node (ref "J1") (pin "4") (pinfunction "4_4") (pintype "passive"))
      (node (ref "R15") (pin "1") (pintype "passive"))
    )
    (net (code "110") (name "Net-(D5-PadK)") (class "Default")
      (node (ref "D5") (pin "K") (pinfunction "K_K") (pintype "passive"))
      (node (ref "J1") (pin "6") (pinfunction "6_6") (pintype "passive"))
      (node (ref "R17") (pin "1") (pintype "passive"))
    )
    (net (code "111") (name "Net-(D6-PadK)") (class "Default")
      (node (ref "D6") (pin "K") (pinfunction "K_K") (pintype "passive"))
      (node (ref "J1") (pin "8") (pinfunction "8_8") (pintype "passive"))
      (node (ref "R19") (pin "1") (pintype "passive"))
    )
    (net (code "112") (name "Net-(D7-PadK)") (class "Default")
      (node (ref "D7") (pin "K") (pinfunction "K_K") (pintype "passive"))
      (node (ref "J1") (pin "10") (pinfunction "10_10") (pintype "passive"))
      (node (ref "R21") (pin "1") (pintype "passive"))
    )
    (net (code "113") (name "Net-(D8-PadK)") (class "Default")
      (node (ref "D8") (pin "K") (pinfunction "K_K") (pintype "passive"))
      (node (ref "J1") (pin "12") (pinfunction "12_12") (pintype "passive"))
      (node (ref "R23") (pin "1") (pintype "passive"))
    )
    (net (code "114") (name "Net-(D9-PadK)") (class "Default")
      (node (ref "D9") (pin "K") (pinfunction "K_K") (pintype "passive"))
      (node (ref "J1") (pin "3") (pinfunction "3_3") (pintype "passive"))
      (node (ref "R14") (pin "2") (pintype "passive"))
    )
    (net (code "115") (name "Net-(D10-PadK)") (class "Default")
      (node (ref "D10") (pin "K") (pinfunction "K_K") (pintype "passive"))
      (node (ref "J1") (pin "5") (pinfunction "5_5") (pintype "passive"))
      (node (ref "R16") (pin "2") (pintype "passive"))
    )
    (net (code "116") (name "Net-(D11-PadK)") (class "Default")
      (node (ref "D11") (pin "K") (pinfunction "K_K") (pintype "passive"))
      (node (ref "J1") (pin "7") (pinfunction "7_7") (pintype "passive"))
      (node (ref "R18") (pin "2") (pintype "passive"))
    )
    (net (code "117") (name "Net-(D12-PadK)") (class "Default")
      (node (ref "D12") (pin "K") (pinfunction "K_K") (pintype "passive"))
      (node (ref "J1") (pin "9") (pinfunction "9_9") (pintype "passive"))
      (node (ref "R20") (pin "2") (pintype "passive"))
    )
    (net (code "118") (name "Net-(D13-PadK)") (class "Default")
      (node (ref "D13") (pin "K") (pinfunction "K_K") (pintype "passive"))
      (node (ref "J1") (pin "11") (pinfunction "11_11") (pintype "passive"))
      (node (ref "R22") (pin "2") (pintype "passive"))
    )
    (net (code "119") (name "Net-(D14-PadK)") (class "Default")
      (node (ref "D14") (pin "K") (pinfunction "K_K") (pintype "passive"))
      (node (ref "J1") (pin "13") (pinfunction "13_13") (pintype "passive"))
      (node (ref "R24") (pin "2") (pintype "passive"))
    )
    (net (code "120") (name "Net-(D16-PadK)") (class "Default")
      (node (ref "D16") (pin "K") (pinfunction "K_K") (pintype "passive"))
      (node (ref "J1") (pin "17") (pinfunction "17_17") (pintype "passive"))
      (node (ref "R26") (pin "2") (pintype "passive"))
    )
    (net (code "121") (name "Net-(LED1-PadK)") (class "Default")
      (node (ref "LED1") (pin "K") (pinfunction "K_K") (pintype "passive"))
      (node (ref "R31") (pin "2") (pintype "passive"))
    )
    (net (code "122") (name "Net-(LED2-PadK)") (class "Default")
      (node (ref "LED2") (pin "K") (pinfunction "K_K") (pintype "passive"))
      (node (ref "R33") (pin "2") (pintype "passive"))
    )
    (net (code "123") (name "Net-(Q1-G)") (class "Default")
      (node (ref "Q1") (pin "1") (pinfunction "G_1") (pintype "passive"))
      (node (ref "R29") (pin "2") (pintype "passive"))
      (node (ref "R30") (pin "2") (pintype "passive"))
    )
    (net (code "124") (name "unconnected-(U2A-PA1-PadP2)") (class "Default")
      (node (ref "U2") (pin "P2") (pinfunction "PA1_P2") (pintype "bidirectional+no_connect"))
    )
    (net (code "125") (name "unconnected-(U2A-PA2-PadR2)") (class "Default")
      (node (ref "U2") (pin "R2") (pinfunction "PA2_R2") (pintype "bidirectional+no_connect"))
    )
    (net (code "126") (name "unconnected-(U2A-PA3-PadN5)") (class "Default")
      (node (ref "U2") (pin "N5") (pinfunction "PA3_N5") (pintype "bidirectional+no_connect"))
    )
    (net (code "127") (name "unconnected-(U2A-PA5-PadP6)") (class "Default")
      (node (ref "U2") (pin "P6") (pinfunction "PA5_P6") (pintype "bidirectional+no_connect"))
    )
    (net (code "128") (name "unconnected-(U2A-PA7-PadN6)") (class "Default")
      (node (ref "U2") (pin "N6") (pinfunction "PA7_N6") (pintype "bidirectional+no_connect"))
    )
    (net (code "129") (name "unconnected-(U2A-PA11-PadC15)") (class "Default")
      (node (ref "U2") (pin "C15") (pinfunction "PA11_C15") (pintype "bidirectional+no_connect"))
    )
    (net (code "130") (name "unconnected-(U2A-PA12-PadB15)") (class "Default")
      (node (ref "U2") (pin "B15") (pinfunction "PA12_B15") (pintype "bidirectional+no_connect"))
    )
    (net (code "131") (name "unconnected-(U2A-PB2-PadP7)") (class "Default")
      (node (ref "U2") (pin "P7") (pinfunction "PB2_P7") (pintype "bidirectional+no_connect"))
    )
    (net (code "132") (name "unconnected-(U2A-PB13-PadL15)") (class "Default")
      (node (ref "U2") (pin "L15") (pinfunction "PB13_L15") (pintype "bidirectional+no_connect"))
    )
    (net (code "133") (name "unconnected-(U2A-PB14-PadK15)") (class "Default")
      (node (ref "U2") (pin "K15") (pinfunction "PB14_K15") (pintype "bidirectional+no_connect"))
    )
    (net (code "134") (name "unconnected-(U2A-PB15-PadK14)") (class "Default")
      (node (ref "U2") (pin "K14") (pinfunction "PB15_K14") (pintype "bidirectional+no_connect"))
    )
    (net (code "135") (name "unconnected-(U2A-PC0-PadL2)") (class "Default")
      (node (ref "U2") (pin "L2") (pinfunction "PC0_L2") (pintype "bidirectional+no_connect"))
    )
    (net (code "136") (name "unconnected-(U2A-PC1-PadL3)") (class "Default")
      (node (ref "U2") (pin "L3") (pinfunction "PC1_L3") (pintype "bidirectional+no_connect"))
    )
    (net (code "137") (name "unconnected-(U2A-PC2-PadM1)") (class "Default")
      (node (ref "U2") (pin "M1") (pinfunction "PC2_M1") (pintype "bidirectional+no_connect"))
    )
    (net (code "138") (name "unconnected-(U2A-PC2_C-PadN1)") (class "Default")
      (node (ref "U2") (pin "N1") (pinfunction "PC2_C_N1") (pintype "input+no_connect"))
    )
    (net (code "139") (name "unconnected-(U2A-PC5-PadM7)") (class "Default")
      (node (ref "U2") (pin "M7") (pinfunction "PC5_M7") (pintype "bidirectional+no_connect"))
    )
    (net (code "140") (name "unconnected-(U2A-PC13-PadC1)") (class "Default")
      (node (ref "U2") (pin "C1") (pinfunction "PC13_C1") (pintype "bidirectional+no_connect"))
    )
    (net (code "141") (name "unconnected-(U2A-PC14-OSC32_IN-PadD2)") (class "Default")
      (node (ref "U2") (pin "D2") (pinfunction "PC14-OSC32_IN_D2") (pintype "bidirectional+no_connect"))
    )
    (net (code "142") (name "unconnected-(U2A-PC15-OSC32_OUT-PadD1)") (class "Default")
      (node (ref "U2") (pin "D1") (pinfunction "PC15-OSC32_OUT_D1") (pintype "bidirectional+no_connect"))
    )
    (net (code "143") (name "unconnected-(U2A-PD0-PadC10)") (class "Default")
      (node (ref "U2") (pin "C10") (pinfunction "PD0_C10") (pintype "bidirectional"))
    )
    (net (code "144") (name "unconnected-(U2A-PD1-PadA10)") (class "Default")
      (node (ref "U2") (pin "A10") (pinfunction "PD1_A10") (pintype "bidirectional"))
    )
    (net (code "145") (name "unconnected-(U2A-PD3-PadA9)") (class "Default")
      (node (ref "U2") (pin "A9") (pinfunction "PD3_A9") (pintype "bidirectional"))
    )
    (net (code "146") (name "unconnected-(U2A-PD4-PadC9)") (class "Default")
      (node (ref "U2") (pin "C9") (pinfunction "PD4_C9") (pintype "bidirectional"))
    )
    (net (code "147") (name "unconnected-(U2B-PE7-PadP9)") (class "Default")
      (node (ref "U2") (pin "P9") (pinfunction "PE7_P9") (pintype "bidirectional+no_connect"))
    )
    (net (code "148") (name "unconnected-(U2B-PF0-PadF4)") (class "Default")
      (node (ref "U2") (pin "F4") (pinfunction "PF0_F4") (pintype "bidirectional+no_connect"))
    )
    (net (code "149") (name "unconnected-(U2B-PF1-PadF3)") (class "Default")
      (node (ref "U2") (pin "F3") (pinfunction "PF1_F3") (pintype "bidirectional+no_connect"))
    )
    (net (code "150") (name "unconnected-(U2B-PF2-PadG3)") (class "Default")
      (node (ref "U2") (pin "G3") (pinfunction "PF2_G3") (pintype "bidirectional+no_connect"))
    )
    (net (code "151") (name "unconnected-(U2B-PF4-PadH2)") (class "Default")
      (node (ref "U2") (pin "H2") (pinfunction "PF4_H2") (pintype "bidirectional+no_connect"))
    )
    (net (code "152") (name "unconnected-(U2B-PF6-PadH1)") (class "Default")
      (node (ref "U2") (pin "H1") (pinfunction "PF6_H1") (pintype "bidirectional+no_connect"))
    )
    (net (code "153") (name "unconnected-(U2B-PF8-PadJ2)") (class "Default")
      (node (ref "U2") (pin "J2") (pinfunction "PF8_J2") (pintype "bidirectional+no_connect"))
    )
    (net (code "154") (name "unconnected-(U2B-PF15-PadN10)") (class "Default")
      (node (ref "U2") (pin "N10") (pinfunction "PF15_N10") (pintype "bidirectional+no_connect"))
    )
    (net (code "155") (name "unconnected-(U2B-PG0-PadP8)") (class "Default")
      (node (ref "U2") (pin "P8") (pinfunction "PG0_P8") (pintype "bidirectional+no_connect"))
    )
    (net (code "156") (name "unconnected-(U2B-PG1-PadN9)") (class "Default")
      (node (ref "U2") (pin "N9") (pinfunction "PG1_N9") (pintype "bidirectional+no_connect"))
    )
    (net (code "157") (name "unconnected-(U2B-PG9-PadA8)") (class "Default")
      (node (ref "U2") (pin "A8") (pinfunction "PG9_A8") (pintype "bidirectional+no_connect"))
    )
    (net (code "158") (name "unconnected-(U2B-PG10-PadC8)") (class "Default")
      (node (ref "U2") (pin "C8") (pinfunction "PG10_C8") (pintype "bidirectional+no_connect"))
    )
    (net (code "159") (name "unconnected-(U2B-PG15-PadD7)") (class "Default")
      (node (ref "U2") (pin "D7") (pinfunction "PG15_D7") (pintype "bidirectional"))
    )
    (net (code "160") (name "unconnected-(U2B-PH0-OSC_IN-PadJ1)") (class "Default")
      (node (ref "U2") (pin "J1") (pinfunction "PH0-OSC_IN_J1") (pintype "bidirectional+no_connect"))
    )
    (net (code "161") (name "unconnected-(U2B-PH1-OSC_OUT-PadK1)") (class "Default")
      (node (ref "U2") (pin "K1") (pinfunction "PH1-OSC_OUT_K1") (pintype "bidirectional+no_connect"))
    )
    (net (code "162") (name "unconnected-(U2B-PH2-PadN4)") (class "Default")
      (node (ref "U2") (pin "N4") (pinfunction "PH2_N4") (pintype "bidirectional+no_connect"))
    )
    (net (code "163") (name "unconnected-(U2B-PH3-PadR4)") (class "Default")
      (node (ref "U2") (pin "R4") (pinfunction "PH3_R4") (pintype "bidirectional+no_connect"))
    )
    (net (code "164") (name "unconnected-(U2B-PH4-PadP4)") (class "Default")
      (node (ref "U2") (pin "P4") (pinfunction "PH4_P4") (pintype "bidirectional+no_connect"))
    )
    (net (code "165") (name "unconnected-(U2B-PH8-PadN13)") (class "Default")
      (node (ref "U2") (pin "N13") (pinfunction "PH8_N13") (pintype "bidirectional+no_connect"))
    )
    (net (code "166") (name "unconnected-(U2B-PH9-PadM14)") (class "Default")
      (node (ref "U2") (pin "M14") (pinfunction "PH9_M14") (pintype "bidirectional+no_connect"))
    )
    (net (code "167") (name "unconnected-(U2B-PH10-PadN14)") (class "Default")
      (node (ref "U2") (pin "N14") (pinfunction "PH10_N14") (pintype "bidirectional+no_connect"))
    )
    (net (code "168") (name "unconnected-(U2B-PH12-PadN15)") (class "Default")
      (node (ref "U2") (pin "N15") (pinfunction "PH12_N15") (pintype "bidirectional+no_connect"))
    )
    (net (code "169") (name "unconnected-(U2B-PH14-PadB12)") (class "Default")
      (node (ref "U2") (pin "B12") (pinfunction "PH14_B12") (pintype "bidirectional+no_connect"))
    )
    (net (code "170") (name "unconnected-(U2B-PH15-PadD12)") (class "Default")
      (node (ref "U2") (pin "D12") (pinfunction "PH15_D12") (pintype "bidirectional+no_connect"))
    )
  )
)
